# Mixer.net
KiCad netlist of a schematic drawn in EAGLE
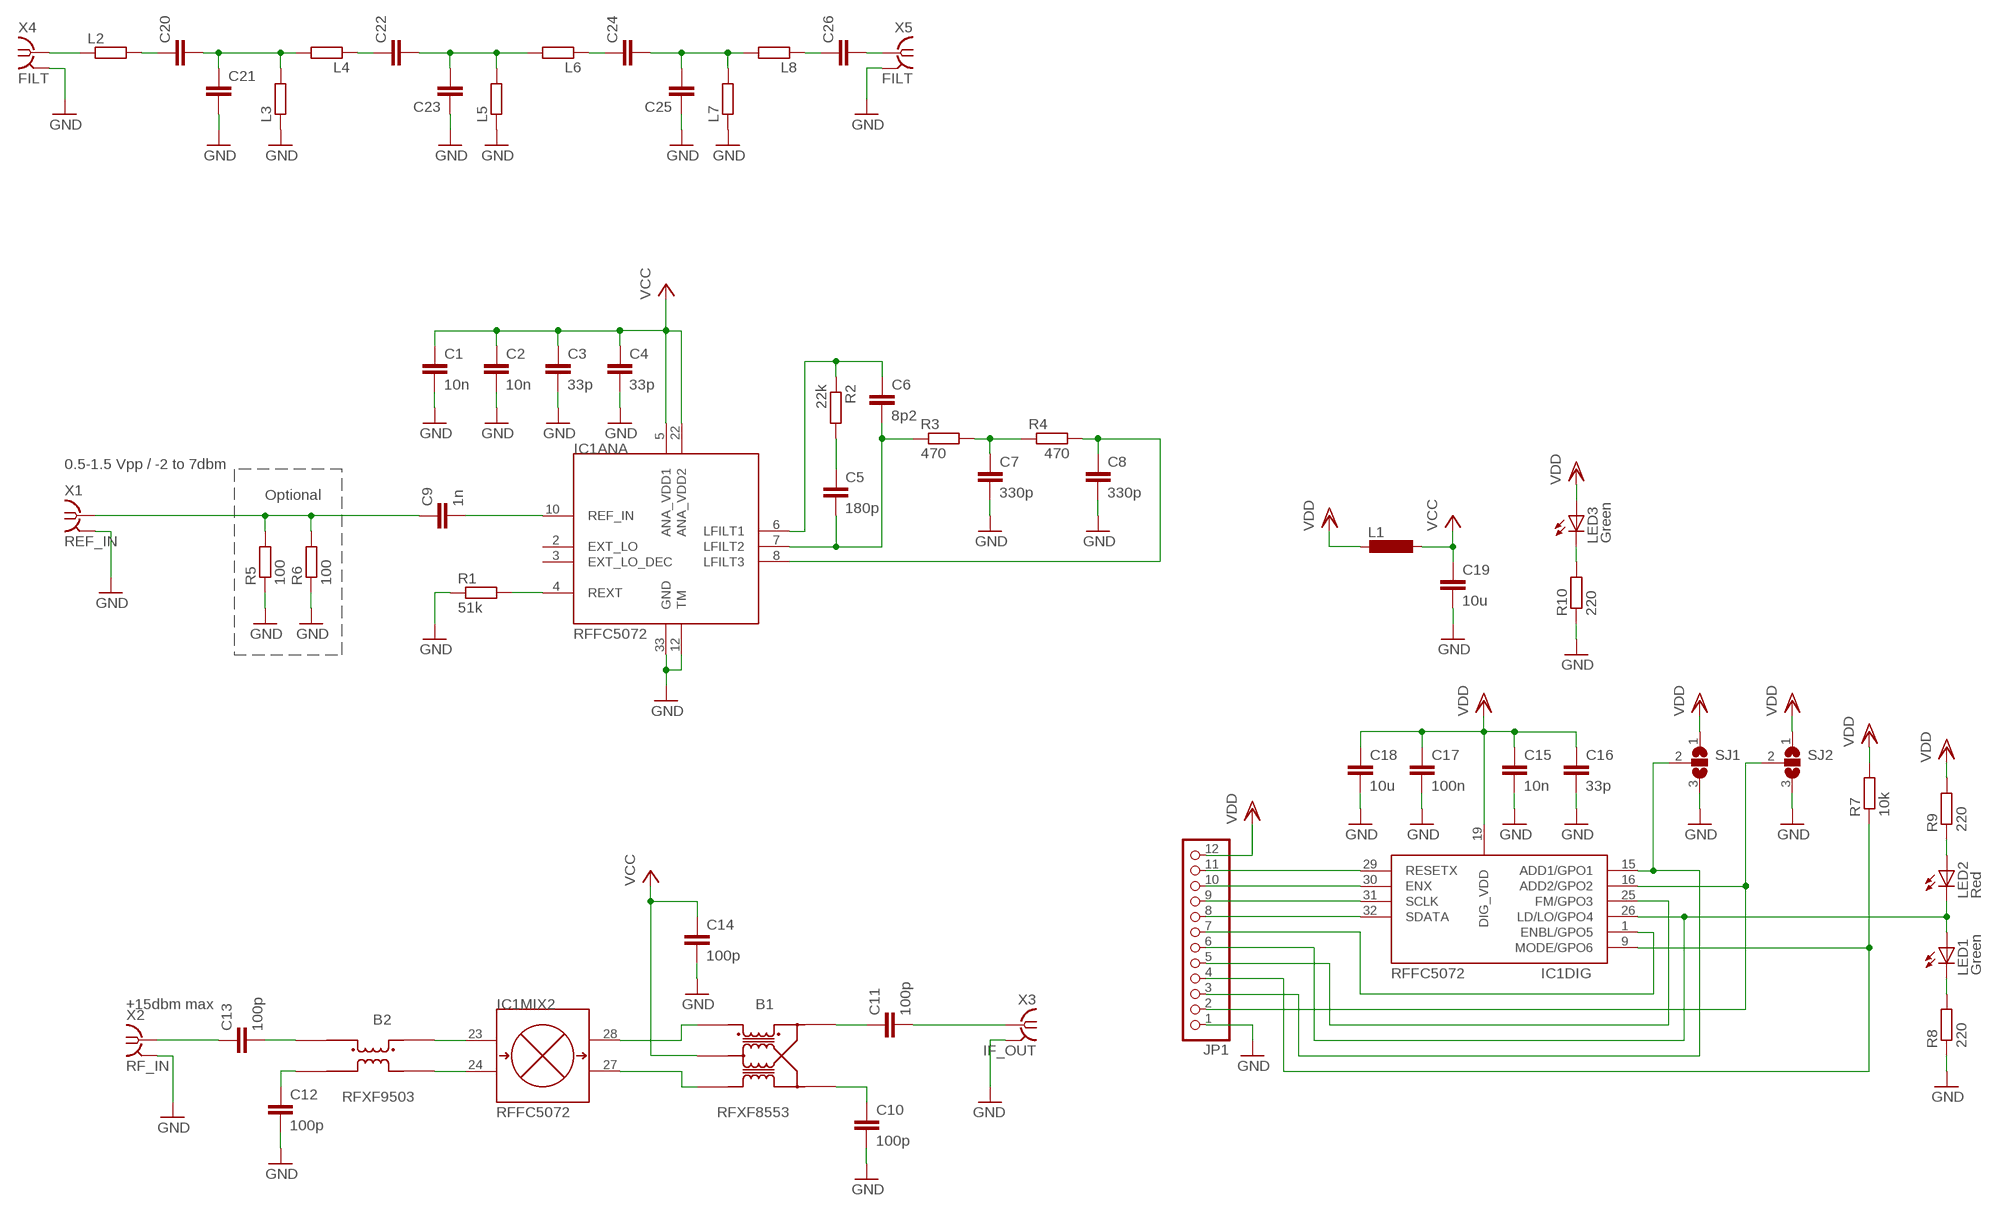
[diagram p0: schematic, sheet 1]

(export (version "E")
  (design (tool "Eeschema 10.0.6"))
  (components
    (comp (ref "B1")
      (value "RFXF8553")
      (footprint "eagle-import:S20")
      (libsource (lib "eagle-import") (part "RFXF8553"))
    )
    (comp (ref "B2")
      (value "RFXF9503")
      (footprint "eagle-import:S20")
      (libsource (lib "eagle-import") (part "RFXF9503"))
    )
    (comp (ref "C1")
      (value "10n")
      (footprint "eagle-import:C0603")
      (libsource (lib "eagle-import") (part "C-EUC0603"))
    )
    (comp (ref "C2")
      (value "10n")
      (footprint "eagle-import:C0603")
      (libsource (lib "eagle-import") (part "C-EUC0603"))
    )
    (comp (ref "C3")
      (value "33p")
      (footprint "eagle-import:C0603")
      (libsource (lib "eagle-import") (part "C-EUC0603"))
    )
    (comp (ref "C4")
      (value "33p")
      (footprint "eagle-import:C0603")
      (libsource (lib "eagle-import") (part "C-EUC0603"))
    )
    (comp (ref "C5")
      (value "180p")
      (footprint "eagle-import:C0603")
      (libsource (lib "eagle-import") (part "C-EUC0603"))
    )
    (comp (ref "C6")
      (value "8p2")
      (footprint "eagle-import:C0603")
      (libsource (lib "eagle-import") (part "C-EUC0603"))
    )
    (comp (ref "C7")
      (value "330p")
      (footprint "eagle-import:C0603")
      (libsource (lib "eagle-import") (part "C-EUC0603"))
    )
    (comp (ref "C8")
      (value "330p")
      (footprint "eagle-import:C0603")
      (libsource (lib "eagle-import") (part "C-EUC0603"))
    )
    (comp (ref "C9")
      (value "1n")
      (footprint "eagle-import:C0603")
      (libsource (lib "eagle-import") (part "C-EUC0603"))
    )
    (comp (ref "C10")
      (value "100p")
      (footprint "eagle-import:C0603")
      (libsource (lib "eagle-import") (part "C-EUC0603"))
    )
    (comp (ref "C11")
      (value "100p")
      (footprint "eagle-import:C0603")
      (libsource (lib "eagle-import") (part "C-EUC0603"))
    )
    (comp (ref "C12")
      (value "100p")
      (footprint "eagle-import:C0603")
      (libsource (lib "eagle-import") (part "C-EUC0603"))
    )
    (comp (ref "C13")
      (value "100p")
      (footprint "eagle-import:C0603")
      (libsource (lib "eagle-import") (part "C-EUC0603"))
    )
    (comp (ref "C14")
      (value "100p")
      (footprint "eagle-import:C0603")
      (libsource (lib "eagle-import") (part "C-EUC0603"))
    )
    (comp (ref "C15")
      (value "10n")
      (footprint "eagle-import:C0603")
      (libsource (lib "eagle-import") (part "C-EUC0603"))
    )
    (comp (ref "C16")
      (value "33p")
      (footprint "eagle-import:C0603")
      (libsource (lib "eagle-import") (part "C-EUC0603"))
    )
    (comp (ref "C17")
      (value "100n")
      (footprint "eagle-import:C0603")
      (libsource (lib "eagle-import") (part "C-EUC0603"))
    )
    (comp (ref "C18")
      (value "10u")
      (footprint "eagle-import:C1206")
      (libsource (lib "eagle-import") (part "C-EUC1206"))
    )
    (comp (ref "C19")
      (value "10u")
      (footprint "eagle-import:C1206")
      (libsource (lib "eagle-import") (part "C-EUC1206"))
    )
    (comp (ref "C20")
      (value "C-EUC0603")
      (footprint "eagle-import:C0603")
      (libsource (lib "eagle-import") (part "C-EUC0603"))
    )
    (comp (ref "C21")
      (value "C-EUC0603")
      (footprint "eagle-import:C0603")
      (libsource (lib "eagle-import") (part "C-EUC0603"))
    )
    (comp (ref "C22")
      (value "C-EUC0603")
      (footprint "eagle-import:C0603")
      (libsource (lib "eagle-import") (part "C-EUC0603"))
    )
    (comp (ref "C23")
      (value "C-EUC0603")
      (footprint "eagle-import:C0603")
      (libsource (lib "eagle-import") (part "C-EUC0603"))
    )
    (comp (ref "C24")
      (value "C-EUC0603")
      (footprint "eagle-import:C0603")
      (libsource (lib "eagle-import") (part "C-EUC0603"))
    )
    (comp (ref "C25")
      (value "C-EUC0603")
      (footprint "eagle-import:C0603")
      (libsource (lib "eagle-import") (part "C-EUC0603"))
    )
    (comp (ref "C26")
      (value "C-EUC0603")
      (footprint "eagle-import:C0603")
      (libsource (lib "eagle-import") (part "C-EUC0603"))
    )
    (comp (ref "IC1")
      (value "RFFC5072")
      (footprint "eagle-import:QFN50P500X500X95-33T370")
      (libsource (lib "eagle-import") (part "RFFC5072"))
    )
    (comp (ref "JP1")
      (value "PINHD-1X12/90")
      (footprint "eagle-import:1X12_90")
      (libsource (lib "eagle-import") (part "PINHD-1X12/90"))
    )
    (comp (ref "L1")
      (value "L-EUL2012C")
      (footprint "eagle-import:L2012C")
      (libsource (lib "eagle-import") (part "L-EUL2012C"))
    )
    (comp (ref "L2")
      (value "R-EU_R0603")
      (footprint "eagle-import:R0603")
      (libsource (lib "eagle-import") (part "R-EU_R0603"))
    )
    (comp (ref "L3")
      (value "R-EU_R0603")
      (footprint "eagle-import:R0603")
      (libsource (lib "eagle-import") (part "R-EU_R0603"))
    )
    (comp (ref "L4")
      (value "R-EU_R0603")
      (footprint "eagle-import:R0603")
      (libsource (lib "eagle-import") (part "R-EU_R0603"))
    )
    (comp (ref "L5")
      (value "R-EU_R0603")
      (footprint "eagle-import:R0603")
      (libsource (lib "eagle-import") (part "R-EU_R0603"))
    )
    (comp (ref "L6")
      (value "R-EU_R0603")
      (footprint "eagle-import:R0603")
      (libsource (lib "eagle-import") (part "R-EU_R0603"))
    )
    (comp (ref "L7")
      (value "R-EU_R0603")
      (footprint "eagle-import:R0603")
      (libsource (lib "eagle-import") (part "R-EU_R0603"))
    )
    (comp (ref "L8")
      (value "R-EU_R0603")
      (footprint "eagle-import:R0603")
      (libsource (lib "eagle-import") (part "R-EU_R0603"))
    )
    (comp (ref "LED1")
      (value "Green")
      (footprint "eagle-import:LED_SML0603")
      (libsource (lib "eagle-import") (part "LED_ESML0603"))
    )
    (comp (ref "LED2")
      (value "Red")
      (footprint "eagle-import:LED_SML0603")
      (libsource (lib "eagle-import") (part "LED_ESML0603"))
    )
    (comp (ref "LED3")
      (value "Green")
      (footprint "eagle-import:LED_SML0603")
      (libsource (lib "eagle-import") (part "LED_ESML0603"))
    )
    (comp (ref "R1")
      (value "51k")
      (footprint "eagle-import:R0603")
      (libsource (lib "eagle-import") (part "R-EU_R0603"))
    )
    (comp (ref "R2")
      (value "22k")
      (footprint "eagle-import:R0603")
      (libsource (lib "eagle-import") (part "R-EU_R0603"))
    )
    (comp (ref "R3")
      (value "470")
      (footprint "eagle-import:R0603")
      (libsource (lib "eagle-import") (part "R-EU_R0603"))
    )
    (comp (ref "R4")
      (value "470")
      (footprint "eagle-import:R0603")
      (libsource (lib "eagle-import") (part "R-EU_R0603"))
    )
    (comp (ref "R5")
      (value "100")
      (footprint "eagle-import:R0603")
      (libsource (lib "eagle-import") (part "R-EU_R0603"))
    )
    (comp (ref "R6")
      (value "100")
      (footprint "eagle-import:R0603")
      (libsource (lib "eagle-import") (part "R-EU_R0603"))
    )
    (comp (ref "R7")
      (value "10k")
      (footprint "eagle-import:R0603")
      (libsource (lib "eagle-import") (part "R-EU_R0603"))
    )
    (comp (ref "R8")
      (value "220")
      (footprint "eagle-import:R0603")
      (libsource (lib "eagle-import") (part "R-EU_R0603"))
    )
    (comp (ref "R9")
      (value "220")
      (footprint "eagle-import:R0603")
      (libsource (lib "eagle-import") (part "R-EU_R0603"))
    )
    (comp (ref "R10")
      (value "220")
      (footprint "eagle-import:R0603")
      (libsource (lib "eagle-import") (part "R-EU_R0603"))
    )
    (comp (ref "SJ1")
      (value "SJ2W")
      (footprint "eagle-import:SJ_2")
      (libsource (lib "eagle-import") (part "SJ2W"))
    )
    (comp (ref "SJ2")
      (value "SJ2W")
      (footprint "eagle-import:SJ_2")
      (libsource (lib "eagle-import") (part "SJ2W"))
    )
    (comp (ref "X1")
      (value "REF_IN")
      (footprint "eagle-import:J502-ND-142-0701-881_886")
      (fields (field (name "MF") "JOHNSON COMPONENTS") (field (name "MPN") "142-0701-881"))
      (libsource (lib "eagle-import") (part "SMA-142-0701-881/886"))
    )
    (comp (ref "X2")
      (value "RF_IN")
      (footprint "eagle-import:J502-ND-142-0701-881_886")
      (fields (field (name "MF") "JOHNSON COMPONENTS") (field (name "MPN") "142-0701-881"))
      (libsource (lib "eagle-import") (part "SMA-142-0701-881/886"))
    )
    (comp (ref "X3")
      (value "IF_OUT")
      (footprint "eagle-import:J502-ND-142-0701-881_886")
      (fields (field (name "MF") "JOHNSON COMPONENTS") (field (name "MPN") "142-0701-881"))
      (libsource (lib "eagle-import") (part "SMA-142-0701-881/886"))
    )
    (comp (ref "X4")
      (value "FILT")
      (footprint "eagle-import:J502-ND-142-0701-881_886")
      (fields (field (name "MF") "JOHNSON COMPONENTS") (field (name "MPN") "142-0701-881"))
      (libsource (lib "eagle-import") (part "SMA-142-0701-881/886"))
    )
    (comp (ref "X5")
      (value "FILT")
      (footprint "eagle-import:J502-ND-142-0701-881_886")
      (fields (field (name "MF") "JOHNSON COMPONENTS") (field (name "MPN") "142-0701-881"))
      (libsource (lib "eagle-import") (part "SMA-142-0701-881/886"))
    )
  )
  (nets
    (net (code "1") (name "GND") (class "Default")
      (node (ref "C1") (pin "2") (pinfunction "2_2") (pintype "passive"))
      (node (ref "C10") (pin "2") (pinfunction "2_2") (pintype "passive"))
      (node (ref "C12") (pin "2") (pinfunction "2_2") (pintype "passive"))
      (node (ref "C14") (pin "2") (pinfunction "2_2") (pintype "passive"))
      (node (ref "C15") (pin "2") (pinfunction "2_2") (pintype "passive"))
      (node (ref "C16") (pin "2") (pinfunction "2_2") (pintype "passive"))
      (node (ref "C17") (pin "2") (pinfunction "2_2") (pintype "passive"))
      (node (ref "C18") (pin "2") (pinfunction "2_2") (pintype "passive"))
      (node (ref "C19") (pin "2") (pinfunction "2_2") (pintype "passive"))
      (node (ref "C2") (pin "2") (pinfunction "2_2") (pintype "passive"))
      (node (ref "C21") (pin "2") (pinfunction "2_2") (pintype "passive"))
      (node (ref "C23") (pin "1") (pinfunction "1_1") (pintype "passive"))
      (node (ref "C25") (pin "1") (pinfunction "1_1") (pintype "passive"))
      (node (ref "C3") (pin "2") (pinfunction "2_2") (pintype "passive"))
      (node (ref "C4") (pin "2") (pinfunction "2_2") (pintype "passive"))
      (node (ref "C7") (pin "2") (pinfunction "2_2") (pintype "passive"))
      (node (ref "C8") (pin "2") (pinfunction "2_2") (pintype "passive"))
      (node (ref "IC1") (pin "12") (pinfunction "TM_12") (pintype "bidirectional"))
      (node (ref "IC1") (pin "33") (pinfunction "GND_33") (pintype "bidirectional"))
      (node (ref "JP1") (pin "1") (pinfunction "1_1") (pintype "passive"))
      (node (ref "L3") (pin "1") (pinfunction "1_1") (pintype "passive"))
      (node (ref "L5") (pin "1") (pinfunction "1_1") (pintype "passive"))
      (node (ref "L7") (pin "1") (pinfunction "1_1") (pintype "passive"))
      (node (ref "R1") (pin "1") (pinfunction "1_1") (pintype "passive"))
      (node (ref "R10") (pin "1") (pinfunction "1_1") (pintype "passive"))
      (node (ref "R5") (pin "1") (pinfunction "1_1") (pintype "passive"))
      (node (ref "R6") (pin "1") (pinfunction "1_1") (pintype "passive"))
      (node (ref "R8") (pin "1") (pinfunction "1_1") (pintype "passive"))
      (node (ref "SJ1") (pin "3") (pinfunction "3_3") (pintype "passive"))
      (node (ref "SJ2") (pin "3") (pinfunction "3_3") (pintype "passive"))
      (node (ref "X1") (pin "G@1") (pinfunction "2_G@1") (pintype "passive"))
      (node (ref "X1") (pin "G@2") (pinfunction "2_G@2") (pintype "passive"))
      (node (ref "X1") (pin "G@3") (pinfunction "2_G@3") (pintype "passive"))
      (node (ref "X1") (pin "G@4") (pinfunction "2_G@4") (pintype "passive"))
      (node (ref "X2") (pin "G@1") (pinfunction "2_G@1") (pintype "passive"))
      (node (ref "X2") (pin "G@2") (pinfunction "2_G@2") (pintype "passive"))
      (node (ref "X2") (pin "G@3") (pinfunction "2_G@3") (pintype "passive"))
      (node (ref "X2") (pin "G@4") (pinfunction "2_G@4") (pintype "passive"))
      (node (ref "X3") (pin "G@1") (pinfunction "2_G@1") (pintype "passive"))
      (node (ref "X3") (pin "G@2") (pinfunction "2_G@2") (pintype "passive"))
      (node (ref "X3") (pin "G@3") (pinfunction "2_G@3") (pintype "passive"))
      (node (ref "X3") (pin "G@4") (pinfunction "2_G@4") (pintype "passive"))
      (node (ref "X4") (pin "G@1") (pinfunction "2_G@1") (pintype "passive"))
      (node (ref "X4") (pin "G@2") (pinfunction "2_G@2") (pintype "passive"))
      (node (ref "X4") (pin "G@3") (pinfunction "2_G@3") (pintype "passive"))
      (node (ref "X4") (pin "G@4") (pinfunction "2_G@4") (pintype "passive"))
      (node (ref "X5") (pin "G@1") (pinfunction "2_G@1") (pintype "passive"))
      (node (ref "X5") (pin "G@2") (pinfunction "2_G@2") (pintype "passive"))
      (node (ref "X5") (pin "G@3") (pinfunction "2_G@3") (pintype "passive"))
      (node (ref "X5") (pin "G@4") (pinfunction "2_G@4") (pintype "passive"))
    )
    (net (code "2") (name "Net-(B1-1)") (class "Default")
      (node (ref "B1") (pin "P$1") (pinfunction "1_P$1") (pintype "bidirectional"))
      (node (ref "IC1") (pin "28") (pinfunction "OPP_28") (pintype "bidirectional"))
    )
    (net (code "3") (name "Net-(B1-3)") (class "Default")
      (node (ref "B1") (pin "P$3") (pinfunction "3_P$3") (pintype "bidirectional"))
      (node (ref "IC1") (pin "27") (pinfunction "OPN_27") (pintype "bidirectional"))
    )
    (net (code "4") (name "Net-(B1-4)") (class "Default")
      (node (ref "B1") (pin "P$4") (pinfunction "4_P$4") (pintype "bidirectional"))
      (node (ref "C11") (pin "1") (pinfunction "1_1") (pintype "passive"))
    )
    (net (code "5") (name "Net-(B1-5)") (class "Default")
      (node (ref "B1") (pin "P$5") (pinfunction "5_P$5") (pintype "bidirectional"))
      (node (ref "C10") (pin "1") (pinfunction "1_1") (pintype "passive"))
    )
    (net (code "6") (name "Net-(B2-1)") (class "Default")
      (node (ref "B2") (pin "P$1") (pinfunction "1_P$1") (pintype "bidirectional"))
      (node (ref "IC1") (pin "24") (pinfunction "IPN_24") (pintype "bidirectional"))
    )
    (net (code "7") (name "Net-(B2-3)") (class "Default")
      (node (ref "B2") (pin "P$3") (pinfunction "3_P$3") (pintype "bidirectional"))
      (node (ref "IC1") (pin "23") (pinfunction "IPP_23") (pintype "bidirectional"))
    )
    (net (code "8") (name "Net-(B2-4)") (class "Default")
      (node (ref "B2") (pin "P$4") (pinfunction "4_P$4") (pintype "bidirectional"))
      (node (ref "C13") (pin "2") (pinfunction "2_2") (pintype "passive"))
    )
    (net (code "9") (name "Net-(B2-5)") (class "Default")
      (node (ref "B2") (pin "P$5") (pinfunction "5_P$5") (pintype "bidirectional"))
      (node (ref "C12") (pin "1") (pinfunction "1_1") (pintype "passive"))
    )
    (net (code "10") (name "Net-(C5-Pad1)") (class "Default")
      (node (ref "C5") (pin "1") (pinfunction "1_1") (pintype "passive"))
      (node (ref "R2") (pin "2") (pinfunction "2_2") (pintype "passive"))
    )
    (net (code "11") (name "Net-(C7-Pad1)") (class "Default")
      (node (ref "C7") (pin "1") (pinfunction "1_1") (pintype "passive"))
      (node (ref "R3") (pin "2") (pinfunction "2_2") (pintype "passive"))
      (node (ref "R4") (pin "1") (pinfunction "1_1") (pintype "passive"))
    )
    (net (code "12") (name "Net-(C9-Pad1)") (class "Default")
      (node (ref "C9") (pin "1") (pinfunction "1_1") (pintype "passive"))
      (node (ref "R5") (pin "2") (pinfunction "2_2") (pintype "passive"))
      (node (ref "R6") (pin "2") (pinfunction "2_2") (pintype "passive"))
      (node (ref "X1") (pin "1") (pinfunction "1_1") (pintype "passive"))
    )
    (net (code "13") (name "Net-(C11-Pad2)") (class "Default")
      (node (ref "C11") (pin "2") (pinfunction "2_2") (pintype "passive"))
      (node (ref "X3") (pin "1") (pinfunction "1_1") (pintype "passive"))
    )
    (net (code "14") (name "Net-(C13-Pad1)") (class "Default")
      (node (ref "C13") (pin "1") (pinfunction "1_1") (pintype "passive"))
      (node (ref "X2") (pin "1") (pinfunction "1_1") (pintype "passive"))
    )
    (net (code "15") (name "Net-(C20-Pad1)") (class "Default")
      (node (ref "C20") (pin "1") (pinfunction "1_1") (pintype "passive"))
      (node (ref "L2") (pin "2") (pinfunction "2_2") (pintype "passive"))
    )
    (net (code "16") (name "Net-(C20-Pad2)") (class "Default")
      (node (ref "C20") (pin "2") (pinfunction "2_2") (pintype "passive"))
      (node (ref "C21") (pin "1") (pinfunction "1_1") (pintype "passive"))
      (node (ref "L3") (pin "2") (pinfunction "2_2") (pintype "passive"))
      (node (ref "L4") (pin "2") (pinfunction "2_2") (pintype "passive"))
    )
    (net (code "17") (name "Net-(C22-Pad1)") (class "Default")
      (node (ref "C22") (pin "1") (pinfunction "1_1") (pintype "passive"))
      (node (ref "L4") (pin "1") (pinfunction "1_1") (pintype "passive"))
    )
    (net (code "18") (name "Net-(C22-Pad2)") (class "Default")
      (node (ref "C22") (pin "2") (pinfunction "2_2") (pintype "passive"))
      (node (ref "C23") (pin "2") (pinfunction "2_2") (pintype "passive"))
      (node (ref "L5") (pin "2") (pinfunction "2_2") (pintype "passive"))
      (node (ref "L6") (pin "2") (pinfunction "2_2") (pintype "passive"))
    )
    (net (code "19") (name "Net-(C24-Pad1)") (class "Default")
      (node (ref "C24") (pin "1") (pinfunction "1_1") (pintype "passive"))
      (node (ref "L6") (pin "1") (pinfunction "1_1") (pintype "passive"))
    )
    (net (code "20") (name "Net-(C24-Pad2)") (class "Default")
      (node (ref "C24") (pin "2") (pinfunction "2_2") (pintype "passive"))
      (node (ref "C25") (pin "2") (pinfunction "2_2") (pintype "passive"))
      (node (ref "L7") (pin "2") (pinfunction "2_2") (pintype "passive"))
      (node (ref "L8") (pin "2") (pinfunction "2_2") (pintype "passive"))
    )
    (net (code "21") (name "Net-(C26-Pad1)") (class "Default")
      (node (ref "C26") (pin "1") (pinfunction "1_1") (pintype "passive"))
      (node (ref "L8") (pin "1") (pinfunction "1_1") (pintype "passive"))
    )
    (net (code "22") (name "Net-(C26-Pad2)") (class "Default")
      (node (ref "C26") (pin "2") (pinfunction "2_2") (pintype "passive"))
      (node (ref "X5") (pin "1") (pinfunction "1_1") (pintype "passive"))
    )
    (net (code "23") (name "Net-(IC1A-LFILT1)") (class "Default")
      (node (ref "C6") (pin "1") (pinfunction "1_1") (pintype "passive"))
      (node (ref "IC1") (pin "6") (pinfunction "LFILT1_6") (pintype "bidirectional"))
      (node (ref "R2") (pin "1") (pinfunction "1_1") (pintype "passive"))
    )
    (net (code "24") (name "Net-(IC1A-LFILT2)") (class "Default")
      (node (ref "C5") (pin "2") (pinfunction "2_2") (pintype "passive"))
      (node (ref "C6") (pin "2") (pinfunction "2_2") (pintype "passive"))
      (node (ref "IC1") (pin "7") (pinfunction "LFILT2_7") (pintype "bidirectional"))
      (node (ref "R3") (pin "1") (pinfunction "1_1") (pintype "passive"))
    )
    (net (code "25") (name "Net-(IC1A-LFILT3)") (class "Default")
      (node (ref "C8") (pin "1") (pinfunction "1_1") (pintype "passive"))
      (node (ref "IC1") (pin "8") (pinfunction "LFILT3_8") (pintype "bidirectional"))
      (node (ref "R4") (pin "2") (pinfunction "2_2") (pintype "passive"))
    )
    (net (code "26") (name "Net-(IC1A-REF_IN)") (class "Default")
      (node (ref "C9") (pin "2") (pinfunction "2_2") (pintype "passive"))
      (node (ref "IC1") (pin "10") (pinfunction "REF_IN_10") (pintype "bidirectional"))
    )
    (net (code "27") (name "Net-(IC1A-REXT)") (class "Default")
      (node (ref "IC1") (pin "4") (pinfunction "REXT_4") (pintype "bidirectional"))
      (node (ref "R1") (pin "2") (pinfunction "2_2") (pintype "passive"))
    )
    (net (code "28") (name "Net-(IC1B-ADD1{slash}GPO1)") (class "Default")
      (node (ref "IC1") (pin "15") (pinfunction "ADD1/GPO1_15") (pintype "bidirectional"))
      (node (ref "JP1") (pin "3") (pinfunction "3_3") (pintype "passive"))
      (node (ref "SJ1") (pin "2") (pinfunction "2_2") (pintype "passive"))
    )
    (net (code "29") (name "Net-(IC1B-ADD2{slash}GPO2)") (class "Default")
      (node (ref "IC1") (pin "16") (pinfunction "ADD2/GPO2_16") (pintype "bidirectional"))
      (node (ref "JP1") (pin "2") (pinfunction "2_2") (pintype "passive"))
      (node (ref "SJ2") (pin "2") (pinfunction "2_2") (pintype "passive"))
    )
    (net (code "30") (name "Net-(IC1B-ENBL{slash}GPO5)") (class "Default")
      (node (ref "IC1") (pin "1") (pinfunction "ENBL/GPO5_1") (pintype "bidirectional"))
      (node (ref "JP1") (pin "7") (pinfunction "7_7") (pintype "passive"))
    )
    (net (code "31") (name "Net-(IC1B-ENX)") (class "Default")
      (node (ref "IC1") (pin "30") (pinfunction "ENX_30") (pintype "bidirectional"))
      (node (ref "JP1") (pin "10") (pinfunction "10_10") (pintype "passive"))
    )
    (net (code "32") (name "Net-(IC1B-FM{slash}GPO3)") (class "Default")
      (node (ref "IC1") (pin "25") (pinfunction "FM/GPO3_25") (pintype "bidirectional"))
      (node (ref "JP1") (pin "5") (pinfunction "5_5") (pintype "passive"))
    )
    (net (code "33") (name "Net-(IC1B-LD{slash}LO{slash}GPO4)") (class "Default")
      (node (ref "IC1") (pin "26") (pinfunction "LD/LO/GPO4_26") (pintype "bidirectional"))
      (node (ref "JP1") (pin "6") (pinfunction "6_6") (pintype "passive"))
      (node (ref "LED1") (pin "A") (pinfunction "A_A") (pintype "passive"))
      (node (ref "LED2") (pin "C") (pinfunction "C_C") (pintype "passive"))
    )
    (net (code "34") (name "Net-(IC1B-MODE{slash}GPO6)") (class "Default")
      (node (ref "IC1") (pin "9") (pinfunction "MODE/GPO6_9") (pintype "bidirectional"))
      (node (ref "JP1") (pin "4") (pinfunction "4_4") (pintype "passive"))
      (node (ref "R7") (pin "1") (pinfunction "1_1") (pintype "passive"))
    )
    (net (code "35") (name "Net-(IC1B-RESETX)") (class "Default")
      (node (ref "IC1") (pin "29") (pinfunction "RESETX_29") (pintype "bidirectional"))
      (node (ref "JP1") (pin "11") (pinfunction "11_11") (pintype "passive"))
    )
    (net (code "36") (name "Net-(IC1B-SCLK)") (class "Default")
      (node (ref "IC1") (pin "31") (pinfunction "SCLK_31") (pintype "bidirectional"))
      (node (ref "JP1") (pin "9") (pinfunction "9_9") (pintype "passive"))
    )
    (net (code "37") (name "Net-(IC1B-SDATA)") (class "Default")
      (node (ref "IC1") (pin "32") (pinfunction "SDATA_32") (pintype "bidirectional"))
      (node (ref "JP1") (pin "8") (pinfunction "8_8") (pintype "passive"))
    )
    (net (code "38") (name "Net-(L2-Pad1)") (class "Default")
      (node (ref "L2") (pin "1") (pinfunction "1_1") (pintype "passive"))
      (node (ref "X4") (pin "1") (pinfunction "1_1") (pintype "passive"))
    )
    (net (code "39") (name "Net-(LED1-PadC)") (class "Default")
      (node (ref "LED1") (pin "C") (pinfunction "C_C") (pintype "passive"))
      (node (ref "R8") (pin "2") (pinfunction "2_2") (pintype "passive"))
    )
    (net (code "40") (name "Net-(LED2-PadA)") (class "Default")
      (node (ref "LED2") (pin "A") (pinfunction "A_A") (pintype "passive"))
      (node (ref "R9") (pin "1") (pinfunction "1_1") (pintype "passive"))
    )
    (net (code "41") (name "Net-(LED3-PadC)") (class "Default")
      (node (ref "LED3") (pin "C") (pinfunction "C_C") (pintype "passive"))
      (node (ref "R10") (pin "2") (pinfunction "2_2") (pintype "passive"))
    )
    (net (code "42") (name "VCC") (class "Default")
      (node (ref "B1") (pin "P$2") (pinfunction "2_P$2") (pintype "bidirectional"))
      (node (ref "C1") (pin "1") (pinfunction "1_1") (pintype "passive"))
      (node (ref "C14") (pin "1") (pinfunction "1_1") (pintype "passive"))
      (node (ref "C19") (pin "1") (pinfunction "1_1") (pintype "passive"))
      (node (ref "C2") (pin "1") (pinfunction "1_1") (pintype "passive"))
      (node (ref "C3") (pin "1") (pinfunction "1_1") (pintype "passive"))
      (node (ref "C4") (pin "1") (pinfunction "1_1") (pintype "passive"))
      (node (ref "IC1") (pin "22") (pinfunction "ANA_VDD2_22") (pintype "bidirectional"))
      (node (ref "IC1") (pin "5") (pinfunction "ANA_VDD1_5") (pintype "bidirectional"))
      (node (ref "L1") (pin "1") (pinfunction "1_1") (pintype "passive"))
    )
    (net (code "43") (name "VDD") (class "Default")
      (node (ref "C15") (pin "1") (pinfunction "1_1") (pintype "passive"))
      (node (ref "C16") (pin "1") (pinfunction "1_1") (pintype "passive"))
      (node (ref "C17") (pin "1") (pinfunction "1_1") (pintype "passive"))
      (node (ref "C18") (pin "1") (pinfunction "1_1") (pintype "passive"))
      (node (ref "IC1") (pin "19") (pinfunction "DIG_VDD_19") (pintype "bidirectional"))
      (node (ref "JP1") (pin "12") (pinfunction "12_12") (pintype "passive"))
      (node (ref "L1") (pin "2") (pinfunction "2_2") (pintype "passive"))
      (node (ref "LED3") (pin "A") (pinfunction "A_A") (pintype "passive"))
      (node (ref "R7") (pin "2") (pinfunction "2_2") (pintype "passive"))
      (node (ref "R9") (pin "2") (pinfunction "2_2") (pintype "passive"))
      (node (ref "SJ1") (pin "1") (pinfunction "1_1") (pintype "passive"))
      (node (ref "SJ2") (pin "1") (pinfunction "1_1") (pintype "passive"))
    )
    (net (code "44") (name "unconnected-(IC1A-EXT_LO-Pad2)") (class "Default")
      (node (ref "IC1") (pin "2") (pinfunction "EXT_LO_2") (pintype "bidirectional"))
    )
    (net (code "45") (name "unconnected-(IC1A-EXT_LO_DEC-Pad3)") (class "Default")
      (node (ref "IC1") (pin "3") (pinfunction "EXT_LO_DEC_3") (pintype "bidirectional"))
    )
  )
)
